# Jar_of_Fireflies.net
KiCad netlist of a schematic drawn in EAGLE
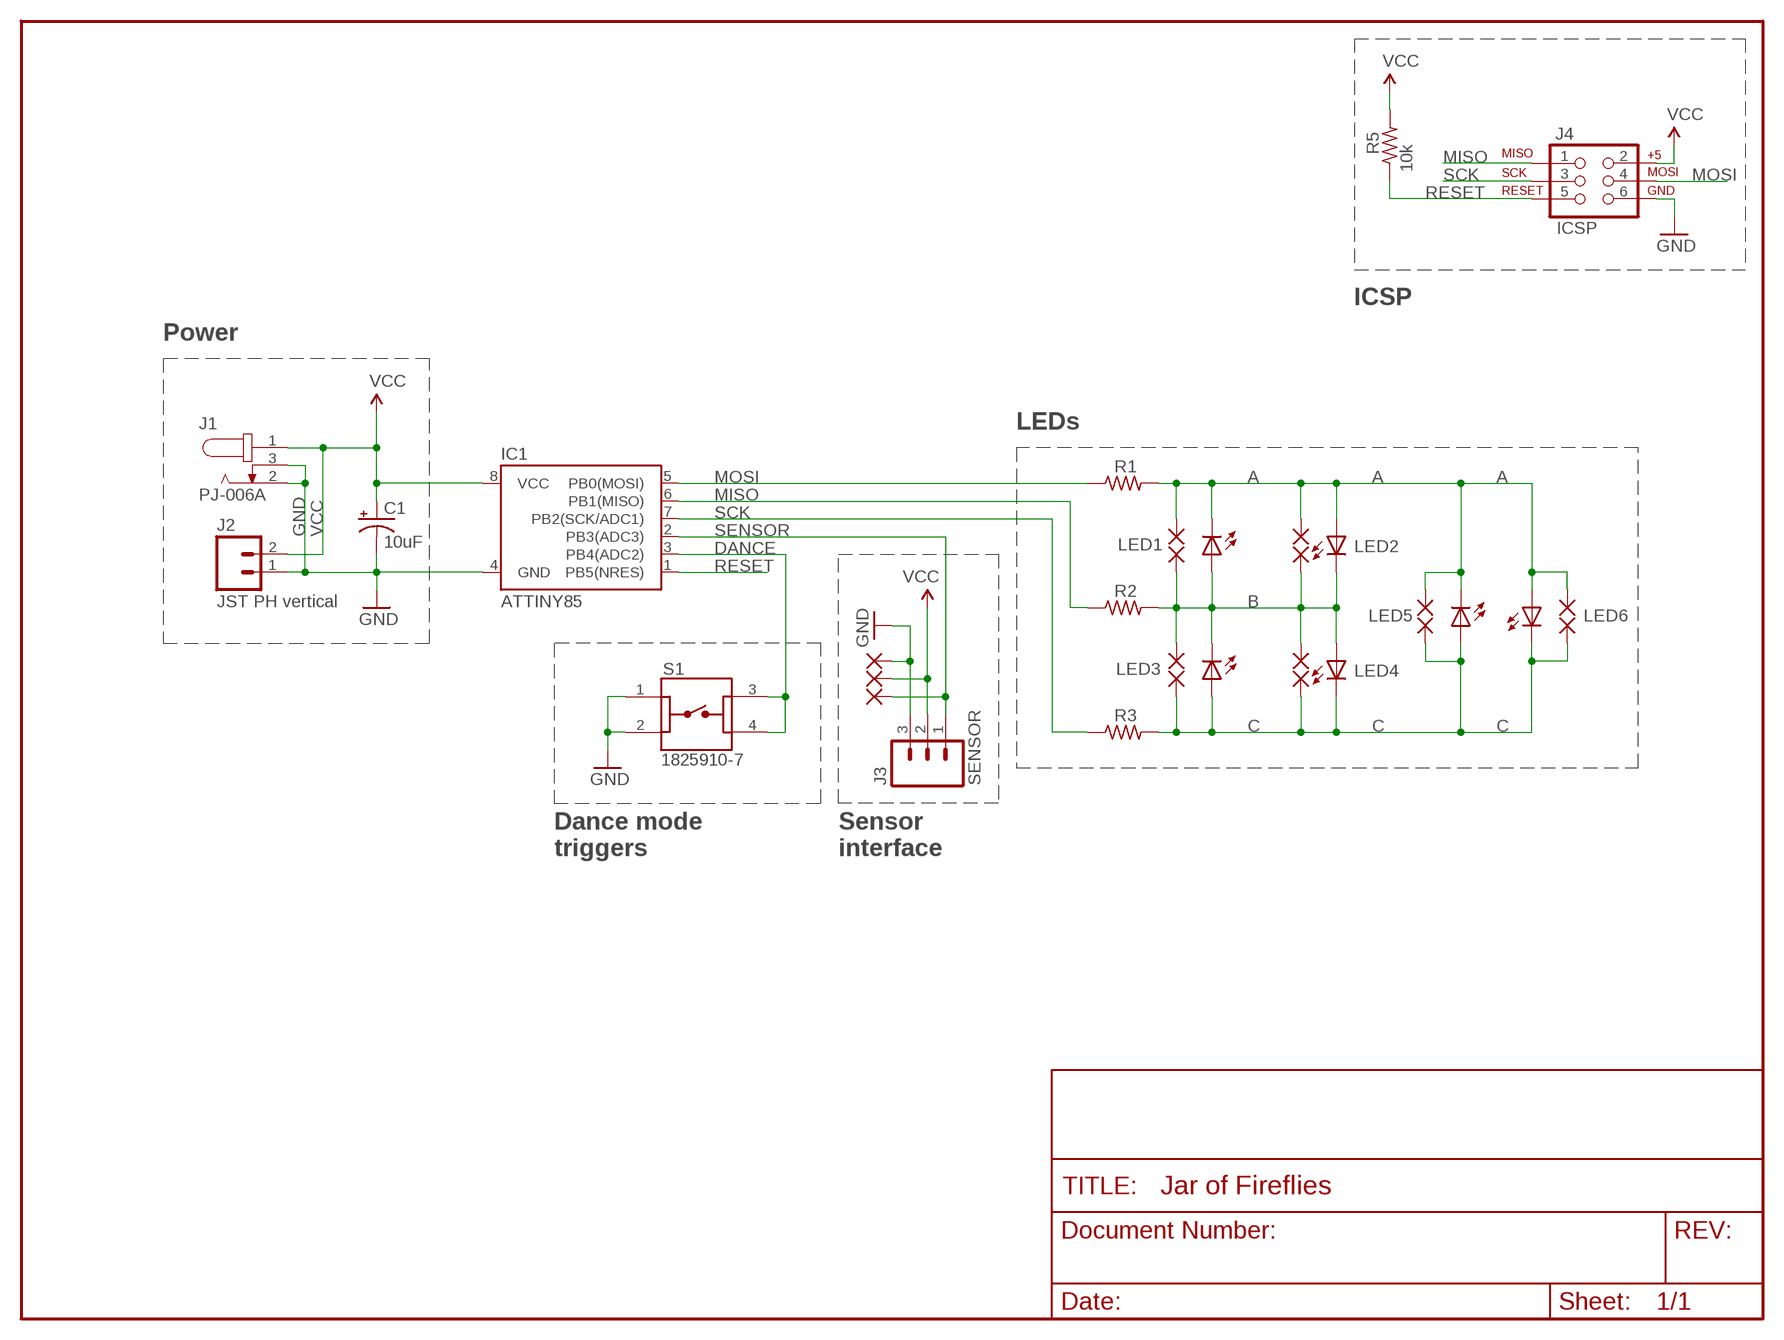
[diagram p0: schematic, sheet 1]

(export (version "E")
  (design (tool "Eeschema 10.0.6"))
  (components
    (comp (ref "C1")
      (value "10uF")
      (footprint "eagle-import:CPOL-RADIAL-10UF-25V")
      (libsource (lib "eagle-import") (part "CAP_POLPTH2"))
    )
    (comp (ref "IC1")
      (value "ATTINY85")
      (footprint "eagle-import:DIP08")
      (libsource (lib "eagle-import") (part "ATTINY45DIP8"))
    )
    (comp (ref "J1")
      (value "PJ-006A")
      (footprint "eagle-import:CUI_PJ-006A")
      (fields (field (name "MANUFACTURER") "CUI INC"))
      (libsource (lib "eagle-import") (part "PJ-006A"))
    )
    (comp (ref "J2")
      (value "JST PH vertical")
      (footprint "eagle-import:JST-2-PTH-VERT")
      (libsource (lib "eagle-import") (part "M02JST-PTH-VERT"))
    )
    (comp (ref "J3")
      (value "SENSOR")
      (footprint "eagle-import:1X03")
      (libsource (lib "eagle-import") (part "M03PTH"))
    )
    (comp (ref "J4")
      (value "ICSP")
      (footprint "eagle-import:2X3_LOCK")
      (libsource (lib "eagle-import") (part "AVR_SPI_PRG_62X3_LOCK"))
    )
    (comp (ref "LED1")
      (value "Amber")
      (footprint "eagle-import:LED5MM")
      (libsource (lib "eagle-import") (part "LED5MM"))
    )
    (comp (ref "LED2")
      (value "Amber")
      (footprint "eagle-import:LED5MM")
      (libsource (lib "eagle-import") (part "LED5MM"))
    )
    (comp (ref "LED3")
      (value "Amber")
      (footprint "eagle-import:LED5MM")
      (libsource (lib "eagle-import") (part "LED5MM"))
    )
    (comp (ref "LED4")
      (value "Amber")
      (footprint "eagle-import:LED5MM")
      (libsource (lib "eagle-import") (part "LED5MM"))
    )
    (comp (ref "LED5")
      (value "Amber")
      (footprint "eagle-import:LED5MM")
      (libsource (lib "eagle-import") (part "LED5MM"))
    )
    (comp (ref "LED6")
      (value "Amber")
      (footprint "eagle-import:LED5MM")
      (libsource (lib "eagle-import") (part "LED5MM"))
    )
    (comp (ref "PAD1")
      (value "SMD2")
      (footprint "eagle-import:SMD1,27-2,54")
      (libsource (lib "eagle-import") (part "SMD2"))
    )
    (comp (ref "PAD2")
      (value "SMD2")
      (footprint "eagle-import:SMD1,27-2,54")
      (libsource (lib "eagle-import") (part "SMD2"))
    )
    (comp (ref "PAD3")
      (value "SMD2")
      (footprint "eagle-import:SMD1,27-2,54")
      (libsource (lib "eagle-import") (part "SMD2"))
    )
    (comp (ref "PAD4")
      (value "SMD2")
      (footprint "eagle-import:SMD1,27-2,54")
      (libsource (lib "eagle-import") (part "SMD2"))
    )
    (comp (ref "PAD5")
      (value "SMD2")
      (footprint "eagle-import:SMD1,27-2,54")
      (libsource (lib "eagle-import") (part "SMD2"))
    )
    (comp (ref "PAD6")
      (value "SMD2")
      (footprint "eagle-import:SMD1,27-2,54")
      (libsource (lib "eagle-import") (part "SMD2"))
    )
    (comp (ref "PAD7")
      (value "SMD2")
      (footprint "eagle-import:SMD1,27-2,54")
      (libsource (lib "eagle-import") (part "SMD2"))
    )
    (comp (ref "PAD8")
      (value "SMD2")
      (footprint "eagle-import:SMD1,27-2,54")
      (libsource (lib "eagle-import") (part "SMD2"))
    )
    (comp (ref "PAD9")
      (value "SMD2")
      (footprint "eagle-import:SMD1,27-2,54")
      (libsource (lib "eagle-import") (part "SMD2"))
    )
    (comp (ref "PAD10")
      (value "SMD2")
      (footprint "eagle-import:SMD1,27-2,54")
      (libsource (lib "eagle-import") (part "SMD2"))
    )
    (comp (ref "PAD11")
      (value "SMD2")
      (footprint "eagle-import:SMD1,27-2,54")
      (libsource (lib "eagle-import") (part "SMD2"))
    )
    (comp (ref "PAD12")
      (value "SMD2")
      (footprint "eagle-import:SMD1,27-2,54")
      (libsource (lib "eagle-import") (part "SMD2"))
    )
    (comp (ref "PAD13")
      (value "WIREPADSMD1,27-254")
      (footprint "eagle-import:SMD1,27-2,54")
      (libsource (lib "eagle-import") (part "WIREPADSMD1,27-254"))
    )
    (comp (ref "PAD14")
      (value "WIREPADSMD1,27-254")
      (footprint "eagle-import:SMD1,27-2,54")
      (libsource (lib "eagle-import") (part "WIREPADSMD1,27-254"))
    )
    (comp (ref "PAD15")
      (value "WIREPADSMD1,27-254")
      (footprint "eagle-import:SMD1,27-2,54")
      (libsource (lib "eagle-import") (part "WIREPADSMD1,27-254"))
    )
    (comp (ref "R1")
      (value "150")
      (footprint "eagle-import:0207_2V")
      (libsource (lib "eagle-import") (part "R-US_0207/2V"))
    )
    (comp (ref "R2")
      (value "150")
      (footprint "eagle-import:0207_2V")
      (libsource (lib "eagle-import") (part "R-US_0207/2V"))
    )
    (comp (ref "R3")
      (value "150")
      (footprint "eagle-import:0207_2V")
      (libsource (lib "eagle-import") (part "R-US_0207/2V"))
    )
    (comp (ref "R5")
      (value "10k")
      (footprint "eagle-import:0207_2V")
      (libsource (lib "eagle-import") (part "R-US_0207/2V"))
    )
    (comp (ref "S1")
      (value "1825910-7")
      (footprint "eagle-import:SW_1825910-7")
      (fields (field (name "DIGI-KEY_PART_NUMBER") "450-1804-ND") (field (name "MF") "TE Connectivity"))
      (libsource (lib "eagle-import") (part "1825910-7"))
    )
  )
  (nets
    (net (code "1") (name "/A") (class "Default")
      (node (ref "LED1") (pin "K") (pinfunction "C_K") (pintype "passive"))
      (node (ref "LED2") (pin "A") (pinfunction "A_A") (pintype "passive"))
      (node (ref "LED5") (pin "K") (pinfunction "C_K") (pintype "passive"))
      (node (ref "LED6") (pin "A") (pinfunction "A_A") (pintype "passive"))
      (node (ref "PAD1") (pin "1") (pinfunction "P_1") (pintype "passive"))
      (node (ref "PAD11") (pin "1") (pinfunction "P_1") (pintype "passive"))
      (node (ref "PAD5") (pin "1") (pinfunction "P_1") (pintype "passive"))
      (node (ref "PAD9") (pin "1") (pinfunction "P_1") (pintype "passive"))
      (node (ref "R1") (pin "2") (pinfunction "2_2") (pintype "passive"))
    )
    (net (code "2") (name "/B") (class "Default")
      (node (ref "LED1") (pin "A") (pinfunction "A_A") (pintype "passive"))
      (node (ref "LED2") (pin "K") (pinfunction "C_K") (pintype "passive"))
      (node (ref "LED3") (pin "K") (pinfunction "C_K") (pintype "passive"))
      (node (ref "LED4") (pin "A") (pinfunction "A_A") (pintype "passive"))
      (node (ref "PAD2") (pin "1") (pinfunction "P_1") (pintype "passive"))
      (node (ref "PAD3") (pin "1") (pinfunction "P_1") (pintype "passive"))
      (node (ref "PAD6") (pin "1") (pinfunction "P_1") (pintype "passive"))
      (node (ref "PAD7") (pin "1") (pinfunction "P_1") (pintype "passive"))
      (node (ref "R2") (pin "2") (pinfunction "2_2") (pintype "passive"))
    )
    (net (code "3") (name "/C") (class "Default")
      (node (ref "LED3") (pin "A") (pinfunction "A_A") (pintype "passive"))
      (node (ref "LED4") (pin "K") (pinfunction "C_K") (pintype "passive"))
      (node (ref "LED5") (pin "A") (pinfunction "A_A") (pintype "passive"))
      (node (ref "LED6") (pin "K") (pinfunction "C_K") (pintype "passive"))
      (node (ref "PAD10") (pin "1") (pinfunction "P_1") (pintype "passive"))
      (node (ref "PAD12") (pin "1") (pinfunction "P_1") (pintype "passive"))
      (node (ref "PAD4") (pin "1") (pinfunction "P_1") (pintype "passive"))
      (node (ref "PAD8") (pin "1") (pinfunction "P_1") (pintype "passive"))
      (node (ref "R3") (pin "2") (pinfunction "2_2") (pintype "passive"))
    )
    (net (code "4") (name "/DANCE") (class "Default")
      (node (ref "IC1") (pin "3") (pinfunction "PB4(ADC2)_3") (pintype "bidirectional"))
      (node (ref "S1") (pin "3") (pinfunction "3_3") (pintype "passive"))
      (node (ref "S1") (pin "4") (pinfunction "4_4") (pintype "passive"))
    )
    (net (code "5") (name "/MISO") (class "Default")
      (node (ref "IC1") (pin "6") (pinfunction "PB1(MISO)_6") (pintype "bidirectional"))
      (node (ref "J4") (pin "1") (pinfunction "1_1") (pintype "passive"))
      (node (ref "R2") (pin "1") (pinfunction "1_1") (pintype "passive"))
    )
    (net (code "6") (name "/MOSI") (class "Default")
      (node (ref "IC1") (pin "5") (pinfunction "PB0(MOSI)_5") (pintype "bidirectional"))
      (node (ref "J4") (pin "4") (pinfunction "4_4") (pintype "passive"))
      (node (ref "R1") (pin "1") (pinfunction "1_1") (pintype "passive"))
    )
    (net (code "7") (name "/RESET") (class "Default")
      (node (ref "IC1") (pin "1") (pinfunction "PB5(NRES)_1") (pintype "bidirectional"))
      (node (ref "J4") (pin "5") (pinfunction "5_5") (pintype "passive"))
      (node (ref "R5") (pin "1") (pinfunction "1_1") (pintype "passive"))
    )
    (net (code "8") (name "/SCK") (class "Default")
      (node (ref "IC1") (pin "7") (pinfunction "PB2(SCK/ADC1)_7") (pintype "bidirectional"))
      (node (ref "J4") (pin "3") (pinfunction "3_3") (pintype "passive"))
      (node (ref "R3") (pin "1") (pinfunction "1_1") (pintype "passive"))
    )
    (net (code "9") (name "/SENSOR") (class "Default")
      (node (ref "IC1") (pin "2") (pinfunction "PB3(ADC3)_2") (pintype "bidirectional"))
      (node (ref "J3") (pin "1") (pinfunction "1_1") (pintype "passive"))
      (node (ref "PAD15") (pin "1") (pinfunction "P_1") (pintype "passive"))
    )
    (net (code "10") (name "GND") (class "Default")
      (node (ref "C1") (pin "2") (pinfunction "-_2") (pintype "passive"))
      (node (ref "IC1") (pin "4") (pinfunction "GND_4") (pintype "bidirectional"))
      (node (ref "J1") (pin "2") (pinfunction "2_2") (pintype "passive"))
      (node (ref "J1") (pin "3") (pinfunction "3_3") (pintype "passive"))
      (node (ref "J2") (pin "1") (pinfunction "1_1") (pintype "passive"))
      (node (ref "J3") (pin "3") (pinfunction "3_3") (pintype "passive"))
      (node (ref "J4") (pin "6") (pinfunction "6_6") (pintype "passive"))
      (node (ref "PAD13") (pin "1") (pinfunction "P_1") (pintype "passive"))
      (node (ref "S1") (pin "1") (pinfunction "1_1") (pintype "passive"))
      (node (ref "S1") (pin "2") (pinfunction "2_2") (pintype "passive"))
    )
    (net (code "11") (name "VCC") (class "Default")
      (node (ref "C1") (pin "1") (pinfunction "+_1") (pintype "passive"))
      (node (ref "IC1") (pin "8") (pinfunction "VCC_8") (pintype "bidirectional"))
      (node (ref "J1") (pin "1") (pinfunction "1_1") (pintype "passive"))
      (node (ref "J2") (pin "2") (pinfunction "2_2") (pintype "passive"))
      (node (ref "J3") (pin "2") (pinfunction "2_2") (pintype "passive"))
      (node (ref "J4") (pin "2") (pinfunction "2_2") (pintype "passive"))
      (node (ref "PAD14") (pin "1") (pinfunction "P_1") (pintype "passive"))
      (node (ref "R5") (pin "2") (pinfunction "2_2") (pintype "passive"))
    )
  )
)
